# ProDoc_Board1_2026-06-09.net
KiCad netlist of a schematic drawn in EasyEDA Pro
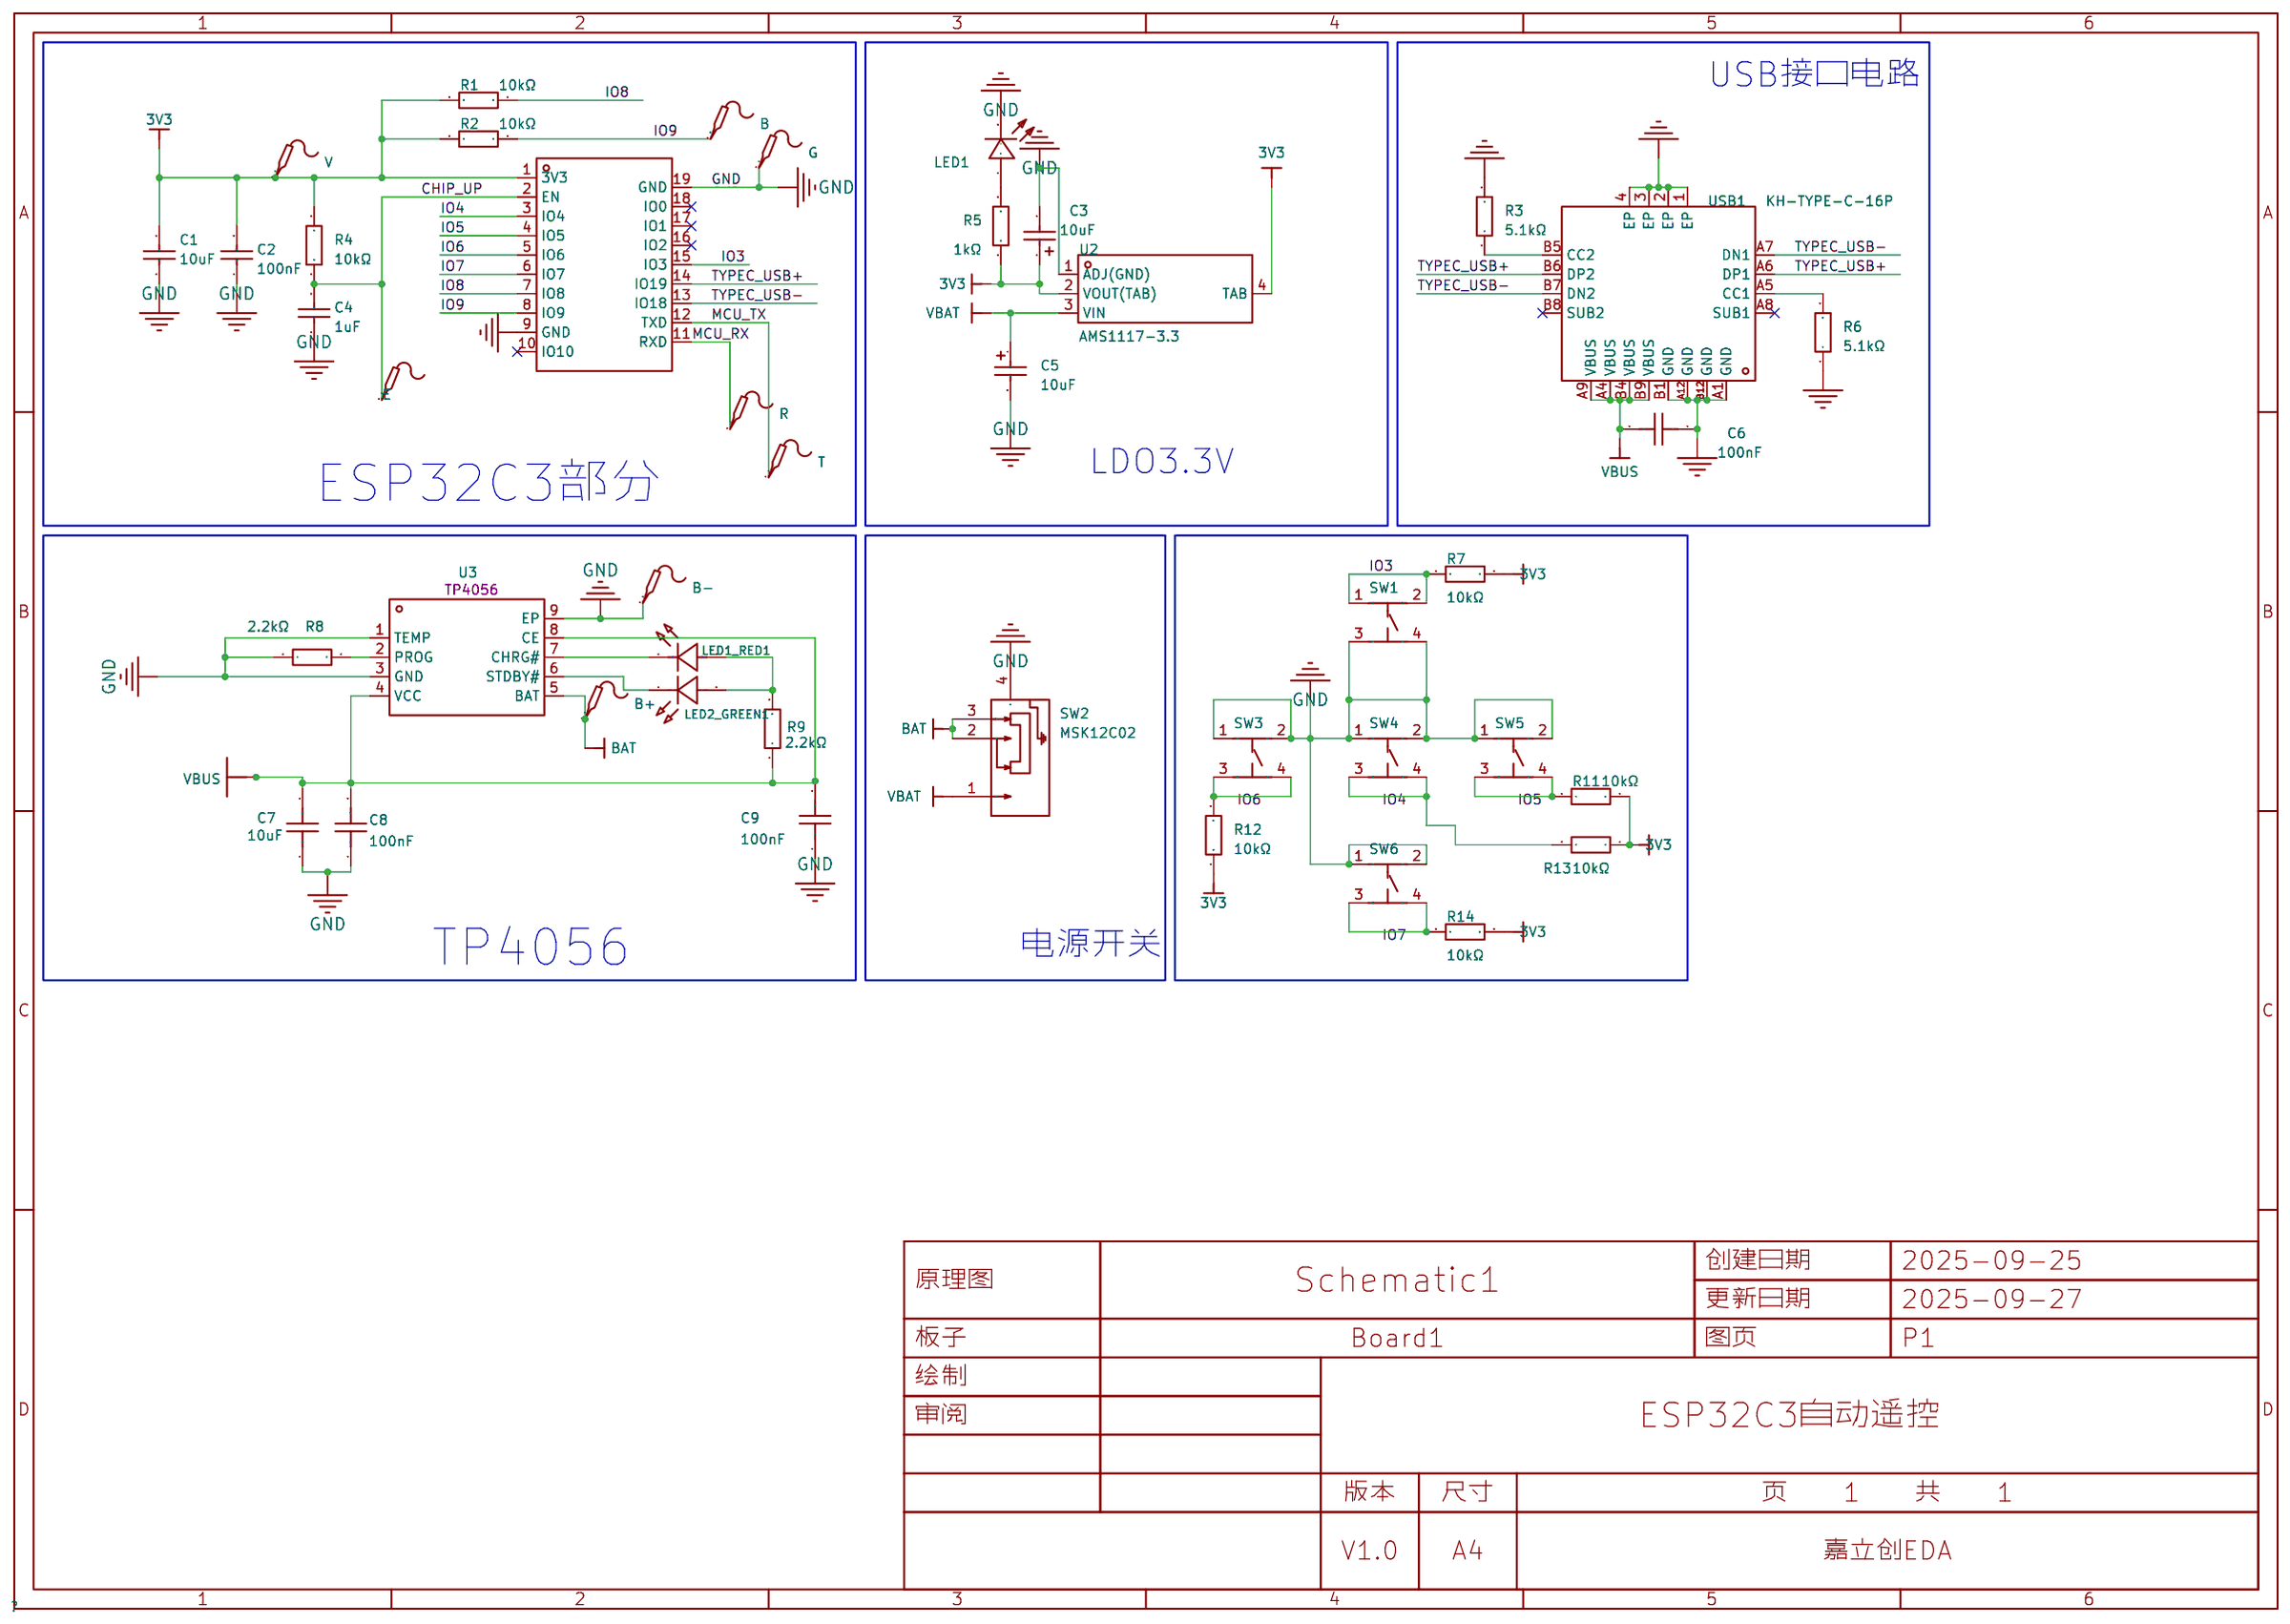
[diagram p0: schematic sheet]

(export (version "E")
  (design (tool "Eeschema 10.0.6"))
  (components
    (comp (ref "B")
      (value "~")
      (footprint "easyedapro:Test-Point-0.5mm")
      (libsource (lib "easyedapro") (part "Test-Point"))
    )
    (comp (ref "B+")
      (value "~")
      (footprint "easyedapro:Test-Point-0.5mm")
      (libsource (lib "easyedapro") (part "Test-Point"))
    )
    (comp (ref "B-")
      (value "~")
      (footprint "easyedapro:Test-Point-0.5mm")
      (libsource (lib "easyedapro") (part "Test-Point"))
    )
    (comp (ref "C1")
      (value "10uF")
      (footprint "easyedapro:C0805")
      (fields
        (field (name "Manufacturer Part") "CL21A106KOQNNNE")
        (field (name "Manufacturer") "SAMSUNG(三星)")
      )
      (libsource (lib "easyedapro") (part "CL21A106KOQNNNE"))
    )
    (comp (ref "C2")
      (value "100nF")
      (footprint "easyedapro:C0805")
      (fields (field (name "Manufacturer Part") "0805B104K500NT") (field (name "Manufacturer") "FH(风华)"))
      (libsource (lib "easyedapro") (part "0805B104K500NT"))
    )
    (comp (ref "C3")
      (value "10uF")
      (footprint "easyedapro:CAP-SMD_L3.2-W1.6-RD-C7171")
      (fields (field (name "Manufacturer Part") "TAJA106K016RNJ") (field (name "Manufacturer") "Kyocera AVX"))
      (libsource (lib "easyedapro") (part "TAJA106K016RNJ"))
    )
    (comp (ref "C4")
      (value "1uF")
      (footprint "easyedapro:C0805")
      (fields
        (field (name "Manufacturer Part") "CL21B105KBFNNNE")
        (field (name "Manufacturer") "SAMSUNG(三星)")
      )
      (libsource (lib "easyedapro") (part "CL21B105KBFNNNE"))
    )
    (comp (ref "C5")
      (value "10uF")
      (footprint "easyedapro:CAP-SMD_L3.2-W1.6-RD-C7171")
      (fields (field (name "Manufacturer Part") "TAJA106K016RNJ") (field (name "Manufacturer") "Kyocera AVX"))
      (libsource (lib "easyedapro") (part "TAJA106K016RNJ"))
    )
    (comp (ref "C6")
      (value "100nF")
      (footprint "easyedapro:C0603")
      (fields
        (field (name "Manufacturer Part") "CC0603KRX7R9BB104")
        (field (name "Manufacturer") "YAGEO(国巨)")
      )
      (libsource (lib "easyedapro") (part "CC0603KRX7R9BB104"))
    )
    (comp (ref "C7")
      (value "10uF")
      (footprint "easyedapro:C0603")
      (fields
        (field (name "Manufacturer Part") "CL10A106KP8NNNC")
        (field (name "Manufacturer") "SAMSUNG(三星)")
      )
      (libsource (lib "easyedapro") (part "CL10A106KP8NNNC"))
    )
    (comp (ref "C8")
      (value "100nF")
      (footprint "easyedapro:C0603")
      (fields
        (field (name "Manufacturer Part") "CC0603KRX7R9BB104")
        (field (name "Manufacturer") "YAGEO(国巨)")
      )
      (libsource (lib "easyedapro") (part "CC0603KRX7R9BB104"))
    )
    (comp (ref "C9")
      (value "100nF")
      (footprint "easyedapro:C0603")
      (fields
        (field (name "Manufacturer Part") "CC0603KRX7R9BB104")
        (field (name "Manufacturer") "YAGEO(国巨)")
      )
      (libsource (lib "easyedapro") (part "CC0603KRX7R9BB104"))
    )
    (comp (ref "E")
      (value "~")
      (footprint "easyedapro:Test-Point-0.5mm")
      (libsource (lib "easyedapro") (part "Test-Point"))
    )
    (comp (ref "G")
      (value "~")
      (footprint "easyedapro:Test-Point-0.5mm")
      (libsource (lib "easyedapro") (part "Test-Point"))
    )
    (comp (ref "LED1")
      (value "NCD0805R1")
      (footprint "easyedapro:LED0805-R-RD")
      (fields (field (name "Manufacturer") "国星光电"))
      (libsource (lib "easyedapro") (part "FC-2012HRK-620D"))
    )
    (comp (ref "LED1_RED1")
      (value "~")
      (footprint "easyedapro:LED0805-RD_RED")
      (fields
        (field (name "Manufacturer Part") "RF-OGB170TS-CB-E0")
        (field (name "Manufacturer") "Refond(瑞丰)")
      )
      (libsource (lib "easyedapro") (part "RF-OGB170TS-CB-E0"))
    )
    (comp (ref "LED2_GREEN1")
      (value "~")
      (footprint "easyedapro:LED0805-RD_GREEN")
      (fields (field (name "Manufacturer Part") "XL-2012UGC") (field (name "Manufacturer") "XINGLIGHT(成兴光)"))
      (libsource (lib "easyedapro") (part "XL-2012UGC"))
    )
    (comp (ref "R")
      (value "~")
      (footprint "easyedapro:Test-Point-0.5mm")
      (libsource (lib "easyedapro") (part "Test-Point"))
    )
    (comp (ref "R1")
      (value "10kΩ")
      (footprint "easyedapro:R0805")
      (fields
        (field (name "Manufacturer Part") "0805W8F1002T5E")
        (field (name "Manufacturer") "UNI-ROYAL(厚声)")
      )
      (libsource (lib "easyedapro") (part "0805W8F1002T5E"))
    )
    (comp (ref "R2")
      (value "10kΩ")
      (footprint "easyedapro:R0805")
      (fields
        (field (name "Manufacturer Part") "0805W8F1002T5E")
        (field (name "Manufacturer") "UNI-ROYAL(厚声)")
      )
      (libsource (lib "easyedapro") (part "0805W8F1002T5E"))
    )
    (comp (ref "R3")
      (value "5.1kΩ")
      (footprint "easyedapro:R0603")
      (fields
        (field (name "Manufacturer Part") "0603WAF5101T5E")
        (field (name "Manufacturer") "UNI-ROYAL(厚声)")
      )
      (libsource (lib "easyedapro") (part "0603WAF5101T5E"))
    )
    (comp (ref "R4")
      (value "10kΩ")
      (footprint "easyedapro:R0805")
      (fields
        (field (name "Manufacturer Part") "0805W8F1002T5E")
        (field (name "Manufacturer") "UNI-ROYAL(厚声)")
      )
      (libsource (lib "easyedapro") (part "0805W8F1002T5E"))
    )
    (comp (ref "R5")
      (value "1kΩ")
      (footprint "easyedapro:R0805")
      (fields (field (name "Manufacturer Part") "RC0805FR-071KL") (field (name "Manufacturer") "YAGEO(国巨)"))
      (libsource (lib "easyedapro") (part "RC0805FR-071KL"))
    )
    (comp (ref "R6")
      (value "5.1kΩ")
      (footprint "easyedapro:R0603")
      (fields
        (field (name "Manufacturer Part") "0603WAF5101T5E")
        (field (name "Manufacturer") "UNI-ROYAL(厚声)")
      )
      (libsource (lib "easyedapro") (part "0603WAF5101T5E"))
    )
    (comp (ref "R7")
      (value "10kΩ")
      (footprint "easyedapro:R0805")
      (fields
        (field (name "Manufacturer Part") "0805W8F1002T5E")
        (field (name "Manufacturer") "UNI-ROYAL(厚声)")
      )
      (libsource (lib "easyedapro") (part "0805W8F1002T5E"))
    )
    (comp (ref "R8")
      (value "2.2kΩ")
      (footprint "easyedapro:R0603")
      (fields
        (field (name "Manufacturer Part") "0603WAF2201T5E")
        (field (name "Manufacturer") "UNI-ROYAL(厚声)")
      )
      (libsource (lib "easyedapro") (part "0603WAF2201T5E"))
    )
    (comp (ref "R9")
      (value "2.2kΩ")
      (footprint "easyedapro:R0603")
      (fields
        (field (name "Manufacturer Part") "0603WAF2201T5E")
        (field (name "Manufacturer") "UNI-ROYAL(厚声)")
      )
      (libsource (lib "easyedapro") (part "0603WAF2201T5E"))
    )
    (comp (ref "R11")
      (value "10kΩ")
      (footprint "easyedapro:R0805")
      (fields
        (field (name "Manufacturer Part") "0805W8F1002T5E")
        (field (name "Manufacturer") "UNI-ROYAL(厚声)")
      )
      (libsource (lib "easyedapro") (part "0805W8F1002T5E"))
    )
    (comp (ref "R12")
      (value "10kΩ")
      (footprint "easyedapro:R0805")
      (fields
        (field (name "Manufacturer Part") "0805W8F1002T5E")
        (field (name "Manufacturer") "UNI-ROYAL(厚声)")
      )
      (libsource (lib "easyedapro") (part "0805W8F1002T5E"))
    )
    (comp (ref "R13")
      (value "10kΩ")
      (footprint "easyedapro:R0805")
      (fields
        (field (name "Manufacturer Part") "0805W8F1002T5E")
        (field (name "Manufacturer") "UNI-ROYAL(厚声)")
      )
      (libsource (lib "easyedapro") (part "0805W8F1002T5E"))
    )
    (comp (ref "R14")
      (value "10kΩ")
      (footprint "easyedapro:R0805")
      (fields
        (field (name "Manufacturer Part") "0805W8F1002T5E")
        (field (name "Manufacturer") "UNI-ROYAL(厚声)")
      )
      (libsource (lib "easyedapro") (part "0805W8F1002T5E"))
    )
    (comp (ref "SW1")
      (value "KH-6X6X5H-STM")
      (footprint "easyedapro:SW-SMD_4P-L6.0-W6.0-P4.50-LS9.0_H5.0")
      (fields (field (name "Manufacturer") "kinghelm(金航标)"))
      (libsource (lib "easyedapro") (part "KH-6X6X5H-STM"))
    )
    (comp (ref "SW2")
      (value "MSK12C02")
      (footprint "easyedapro:SW-TH_MSK12C02")
      (fields (field (name "Manufacturer") "SHOU HAN(首韩)"))
      (libsource (lib "easyedapro") (part "MSK12C02"))
    )
    (comp (ref "SW3")
      (value "KH-6X6X5H-STM")
      (footprint "easyedapro:SW-SMD_4P-L6.0-W6.0-P4.50-LS9.0_H5.0")
      (fields (field (name "Manufacturer") "kinghelm(金航标)"))
      (libsource (lib "easyedapro") (part "KH-6X6X5H-STM"))
    )
    (comp (ref "SW4")
      (value "KH-6X6X5H-STM")
      (footprint "easyedapro:SW-SMD_4P-L6.0-W6.0-P4.50-LS9.0_H5.0")
      (fields (field (name "Manufacturer") "kinghelm(金航标)"))
      (libsource (lib "easyedapro") (part "KH-6X6X5H-STM"))
    )
    (comp (ref "SW5")
      (value "KH-6X6X5H-STM")
      (footprint "easyedapro:SW-SMD_4P-L6.0-W6.0-P4.50-LS9.0_H5.0")
      (fields (field (name "Manufacturer") "kinghelm(金航标)"))
      (libsource (lib "easyedapro") (part "KH-6X6X5H-STM"))
    )
    (comp (ref "SW6")
      (value "KH-6X6X5H-STM")
      (footprint "easyedapro:SW-SMD_4P-L6.0-W6.0-P4.50-LS9.0_H5.0")
      (fields (field (name "Manufacturer") "kinghelm(金航标)"))
      (libsource (lib "easyedapro") (part "KH-6X6X5H-STM"))
    )
    (comp (ref "T")
      (value "~")
      (footprint "easyedapro:Test-Point-0.5mm")
      (libsource (lib "easyedapro") (part "Test-Point"))
    )
    (comp (ref "U1")
      (value "ESP32-C3-WROOM-02-H4")
      (footprint "easyedapro:WIFIM-SMD_18P-L20.0-W18.0-P1.50")
      (fields (field (name "Manufacturer") "ESPRESSIF(乐鑫)"))
      (libsource (lib "easyedapro") (part "ESP32-C3-WROOM-02-H4"))
    )
    (comp (ref "U2")
      (value "AMS1117-3.3")
      (footprint "easyedapro:SOT-223-4_L6.5-W3.5-P2.30-LS7.0-BR")
      (description "输出类型:固定;最大输入电压:18V;输出电压:3.3V;输出电流:1A;电源纹波抑制比(PSRR):60dB@(120Hz);输出极性:正极;")
      (fields (field (name "Manufacturer") "UMW(友台半导体)"))
      (libsource (lib "easyedapro") (part "AMS1117-3.3_C347222"))
    )
    (comp (ref "U3")
      (value "~")
      (footprint "easyedapro:ESOP-8_L4.9-W3.9-P1.27-LS6.0-BL-EP")
      (description "充电电池的类型:-;电池单元组数:-;最大充电电流:-;充满的电池组电压:-;最大供应电压:-;")
      (fields (field (name "Manufacturer Part") "TP4056") (field (name "Manufacturer") "TPOWER(天源)"))
      (libsource (lib "easyedapro") (part "TP4056_C382139"))
    )
    (comp (ref "USB1")
      (value "KH-TYPE-C-16P")
      (footprint "easyedapro:USB-C-SMD_KH-TYPE-C-16P")
      (fields (field (name "Manufacturer") "kinghelm(金航标)"))
      (libsource (lib "easyedapro") (part "KH-TYPE-C-16P"))
    )
    (comp (ref "V")
      (value "~")
      (footprint "easyedapro:Test-Point-0.5mm")
      (libsource (lib "easyedapro") (part "Test-Point"))
    )
  )
  (nets
    (net (code "1") (name "/CHIP_UP") (class "Default")
      (node (ref "C4") (pin "2") (pinfunction "2_2") (pintype "input"))
      (node (ref "E") (pin "1") (pinfunction "1_1") (pintype "input"))
      (node (ref "R4") (pin "1") (pinfunction "1_1") (pintype "input"))
      (node (ref "U1") (pin "2") (pinfunction "EN_2") (pintype "unspecified"))
    )
    (net (code "2") (name "/IO3") (class "Default")
      (node (ref "R7") (pin "2") (pinfunction "2_2") (pintype "input"))
      (node (ref "SW1") (pin "1") (pinfunction "1_1") (pintype "unspecified"))
      (node (ref "SW1") (pin "2") (pinfunction "2_2") (pintype "unspecified"))
      (node (ref "U1") (pin "15") (pinfunction "IO3_15") (pintype "unspecified"))
    )
    (net (code "3") (name "/IO4") (class "Default")
      (node (ref "R13") (pin "2") (pinfunction "2_2") (pintype "input"))
      (node (ref "SW4") (pin "3") (pinfunction "3_3") (pintype "unspecified"))
      (node (ref "SW4") (pin "4") (pinfunction "4_4") (pintype "unspecified"))
      (node (ref "U1") (pin "3") (pinfunction "IO4_3") (pintype "unspecified"))
    )
    (net (code "4") (name "/IO5") (class "Default")
      (node (ref "R11") (pin "2") (pinfunction "2_2") (pintype "input"))
      (node (ref "SW5") (pin "3") (pinfunction "3_3") (pintype "unspecified"))
      (node (ref "SW5") (pin "4") (pinfunction "4_4") (pintype "unspecified"))
      (node (ref "U1") (pin "4") (pinfunction "IO5_4") (pintype "unspecified"))
    )
    (net (code "5") (name "/IO6") (class "Default")
      (node (ref "R12") (pin "2") (pinfunction "2_2") (pintype "input"))
      (node (ref "SW3") (pin "3") (pinfunction "3_3") (pintype "unspecified"))
      (node (ref "SW3") (pin "4") (pinfunction "4_4") (pintype "unspecified"))
      (node (ref "U1") (pin "5") (pinfunction "IO6_5") (pintype "unspecified"))
    )
    (net (code "6") (name "/IO7") (class "Default")
      (node (ref "R14") (pin "2") (pinfunction "2_2") (pintype "input"))
      (node (ref "SW6") (pin "3") (pinfunction "3_3") (pintype "unspecified"))
      (node (ref "SW6") (pin "4") (pinfunction "4_4") (pintype "unspecified"))
      (node (ref "U1") (pin "6") (pinfunction "IO7_6") (pintype "unspecified"))
    )
    (net (code "7") (name "/IO8") (class "Default")
      (node (ref "R1") (pin "1") (pinfunction "1_1") (pintype "input"))
      (node (ref "U1") (pin "7") (pinfunction "IO8_7") (pintype "unspecified"))
    )
    (net (code "8") (name "/IO9") (class "Default")
      (node (ref "B") (pin "1") (pinfunction "1_1") (pintype "input"))
      (node (ref "R2") (pin "1") (pinfunction "1_1") (pintype "input"))
      (node (ref "U1") (pin "8") (pinfunction "IO9_8") (pintype "unspecified"))
    )
    (net (code "9") (name "/MCU_RX") (class "Default")
      (node (ref "R") (pin "1") (pinfunction "1_1") (pintype "input"))
      (node (ref "U1") (pin "11") (pinfunction "RXD_11") (pintype "unspecified"))
    )
    (net (code "10") (name "/MCU_TX") (class "Default")
      (node (ref "T") (pin "1") (pinfunction "1_1") (pintype "input"))
      (node (ref "U1") (pin "12") (pinfunction "TXD_12") (pintype "unspecified"))
    )
    (net (code "11") (name "/TYPEC_USB+") (class "Default")
      (node (ref "U1") (pin "14") (pinfunction "IO19_14") (pintype "unspecified"))
      (node (ref "USB1") (pin "A6") (pinfunction "DP1_A6") (pintype "input"))
      (node (ref "USB1") (pin "B6") (pinfunction "DP2_B6") (pintype "input"))
    )
    (net (code "12") (name "/TYPEC_USB-") (class "Default")
      (node (ref "U1") (pin "13") (pinfunction "IO18_13") (pintype "unspecified"))
      (node (ref "USB1") (pin "A7") (pinfunction "DN1_A7") (pintype "input"))
      (node (ref "USB1") (pin "B7") (pinfunction "DN2_B7") (pintype "input"))
    )
    (net (code "13") (name "3V3") (class "Default")
      (node (ref "C1") (pin "2") (pinfunction "2_2") (pintype "input"))
      (node (ref "C2") (pin "2") (pinfunction "2_2") (pintype "input"))
      (node (ref "C3") (pin "1") (pinfunction "1_1") (pintype "input"))
      (node (ref "R1") (pin "2") (pinfunction "2_2") (pintype "input"))
      (node (ref "R11") (pin "1") (pinfunction "1_1") (pintype "input"))
      (node (ref "R12") (pin "1") (pinfunction "1_1") (pintype "input"))
      (node (ref "R13") (pin "1") (pinfunction "1_1") (pintype "input"))
      (node (ref "R14") (pin "1") (pinfunction "1_1") (pintype "input"))
      (node (ref "R2") (pin "2") (pinfunction "2_2") (pintype "input"))
      (node (ref "R4") (pin "2") (pinfunction "2_2") (pintype "input"))
      (node (ref "R5") (pin "1") (pinfunction "1_1") (pintype "input"))
      (node (ref "R7") (pin "1") (pinfunction "1_1") (pintype "input"))
      (node (ref "U1") (pin "1") (pinfunction "3V3_1") (pintype "unspecified"))
      (node (ref "U2") (pin "2") (pinfunction "VOUT(TAB)_2") (pintype "input"))
      (node (ref "U2") (pin "4") (pinfunction "TAB_4") (pintype "input"))
      (node (ref "V") (pin "1") (pinfunction "1_1") (pintype "input"))
    )
    (net (code "14") (name "BAT") (class "Default")
      (node (ref "B+") (pin "1") (pinfunction "1_1") (pintype "input"))
      (node (ref "SW2") (pin "2") (pinfunction "2_2") (pintype "unspecified"))
      (node (ref "SW2") (pin "3") (pinfunction "3_3") (pintype "unspecified"))
      (node (ref "U3") (pin "5") (pinfunction "BAT_5") (pintype "input"))
    )
    (net (code "15") (name "GND") (class "Default")
      (node (ref "B-") (pin "1") (pinfunction "1_1") (pintype "input"))
      (node (ref "C1") (pin "1") (pinfunction "1_1") (pintype "input"))
      (node (ref "C2") (pin "1") (pinfunction "1_1") (pintype "input"))
      (node (ref "C3") (pin "2") (pinfunction "2_2") (pintype "input"))
      (node (ref "C4") (pin "1") (pinfunction "1_1") (pintype "input"))
      (node (ref "C5") (pin "2") (pinfunction "2_2") (pintype "input"))
      (node (ref "C6") (pin "1") (pinfunction "1_1") (pintype "unspecified"))
      (node (ref "C7") (pin "1") (pinfunction "1_1") (pintype "unspecified"))
      (node (ref "C8") (pin "1") (pinfunction "1_1") (pintype "unspecified"))
      (node (ref "C9") (pin "1") (pinfunction "1_1") (pintype "unspecified"))
      (node (ref "G") (pin "1") (pinfunction "1_1") (pintype "input"))
      (node (ref "LED1") (pin "2") (pinfunction "-_2") (pintype "unspecified"))
      (node (ref "R3") (pin "2") (pinfunction "2_2") (pintype "input"))
      (node (ref "R6") (pin "1") (pinfunction "1_1") (pintype "input"))
      (node (ref "R8") (pin "1") (pinfunction "1_1") (pintype "input"))
      (node (ref "SW1") (pin "3") (pinfunction "3_3") (pintype "unspecified"))
      (node (ref "SW1") (pin "4") (pinfunction "4_4") (pintype "unspecified"))
      (node (ref "SW2") (pin "4") (pinfunction "4_4") (pintype "unspecified"))
      (node (ref "SW3") (pin "1") (pinfunction "1_1") (pintype "unspecified"))
      (node (ref "SW3") (pin "2") (pinfunction "2_2") (pintype "unspecified"))
      (node (ref "SW4") (pin "1") (pinfunction "1_1") (pintype "unspecified"))
      (node (ref "SW4") (pin "2") (pinfunction "2_2") (pintype "unspecified"))
      (node (ref "SW5") (pin "1") (pinfunction "1_1") (pintype "unspecified"))
      (node (ref "SW5") (pin "2") (pinfunction "2_2") (pintype "unspecified"))
      (node (ref "SW6") (pin "1") (pinfunction "1_1") (pintype "unspecified"))
      (node (ref "SW6") (pin "2") (pinfunction "2_2") (pintype "unspecified"))
      (node (ref "U1") (pin "19") (pinfunction "GND_19") (pintype "unspecified"))
      (node (ref "U1") (pin "9") (pinfunction "GND_9") (pintype "unspecified"))
      (node (ref "U2") (pin "1") (pinfunction "ADJ(GND)_1") (pintype "input"))
      (node (ref "U3") (pin "1") (pinfunction "TEMP_1") (pintype "input"))
      (node (ref "U3") (pin "3") (pinfunction "GND_3") (pintype "input"))
      (node (ref "U3") (pin "9") (pinfunction "EP_9") (pintype "input"))
      (node (ref "USB1") (pin "1") (pinfunction "EP_1") (pintype "input"))
      (node (ref "USB1") (pin "2") (pinfunction "EP_2") (pintype "input"))
      (node (ref "USB1") (pin "3") (pinfunction "EP_3") (pintype "input"))
      (node (ref "USB1") (pin "4") (pinfunction "EP_4") (pintype "input"))
      (node (ref "USB1") (pin "A1") (pinfunction "GND_A1") (pintype "input"))
      (node (ref "USB1") (pin "A12") (pinfunction "GND_A12") (pintype "input"))
      (node (ref "USB1") (pin "B1") (pinfunction "GND_B1") (pintype "input"))
      (node (ref "USB1") (pin "B12") (pinfunction "GND_B12") (pintype "input"))
    )
    (net (code "16") (name "Net-(LED1-+)") (class "Default")
      (node (ref "LED1") (pin "1") (pinfunction "+_1") (pintype "unspecified"))
      (node (ref "R5") (pin "2") (pinfunction "2_2") (pintype "input"))
    )
    (net (code "17") (name "Net-(LED1_RED1-A)") (class "Default")
      (node (ref "LED1_RED1") (pin "2") (pinfunction "A_2") (pintype "input"))
      (node (ref "LED2_GREEN1") (pin "2") (pinfunction "A_2") (pintype "input"))
      (node (ref "R9") (pin "2") (pinfunction "2_2") (pintype "input"))
    )
    (net (code "18") (name "Net-(LED1_RED1-K)") (class "Default")
      (node (ref "LED1_RED1") (pin "1") (pinfunction "K_1") (pintype "input"))
      (node (ref "U3") (pin "7") (pinfunction "CHRG#_7") (pintype "input"))
    )
    (net (code "19") (name "Net-(LED2_GREEN1-K)") (class "Default")
      (node (ref "LED2_GREEN1") (pin "1") (pinfunction "K_1") (pintype "input"))
      (node (ref "U3") (pin "6") (pinfunction "STDBY#_6") (pintype "input"))
    )
    (net (code "20") (name "Net-(U3-PROG)") (class "Default")
      (node (ref "R8") (pin "2") (pinfunction "2_2") (pintype "input"))
      (node (ref "U3") (pin "2") (pinfunction "PROG_2") (pintype "input"))
    )
    (net (code "21") (name "Net-(USB1-CC1)") (class "Default")
      (node (ref "R6") (pin "2") (pinfunction "2_2") (pintype "input"))
      (node (ref "USB1") (pin "A5") (pinfunction "CC1_A5") (pintype "input"))
    )
    (net (code "22") (name "Net-(USB1-CC2)") (class "Default")
      (node (ref "R3") (pin "1") (pinfunction "1_1") (pintype "input"))
      (node (ref "USB1") (pin "B5") (pinfunction "CC2_B5") (pintype "input"))
    )
    (net (code "23") (name "VBAT") (class "Default")
      (node (ref "C5") (pin "1") (pinfunction "1_1") (pintype "input"))
      (node (ref "SW2") (pin "1") (pinfunction "1_1") (pintype "unspecified"))
      (node (ref "U2") (pin "3") (pinfunction "VIN_3") (pintype "input"))
    )
    (net (code "24") (name "VBUS") (class "Default")
      (node (ref "C6") (pin "2") (pinfunction "2_2") (pintype "unspecified"))
      (node (ref "C7") (pin "2") (pinfunction "2_2") (pintype "unspecified"))
      (node (ref "C8") (pin "2") (pinfunction "2_2") (pintype "unspecified"))
      (node (ref "C9") (pin "2") (pinfunction "2_2") (pintype "unspecified"))
      (node (ref "R9") (pin "1") (pinfunction "1_1") (pintype "input"))
      (node (ref "U3") (pin "4") (pinfunction "VCC_4") (pintype "input"))
      (node (ref "U3") (pin "8") (pinfunction "CE_8") (pintype "input"))
      (node (ref "USB1") (pin "A4") (pinfunction "VBUS_A4") (pintype "input"))
      (node (ref "USB1") (pin "A9") (pinfunction "VBUS_A9") (pintype "input"))
      (node (ref "USB1") (pin "B4") (pinfunction "VBUS_B4") (pintype "input"))
      (node (ref "USB1") (pin "B9") (pinfunction "VBUS_B9") (pintype "input"))
    )
    (net (code "25") (name "unconnected-(U1-IO0-Pad18)") (class "Default")
      (node (ref "U1") (pin "18") (pinfunction "IO0_18") (pintype "unspecified+no_connect"))
    )
    (net (code "26") (name "unconnected-(U1-IO1-Pad17)") (class "Default")
      (node (ref "U1") (pin "17") (pinfunction "IO1_17") (pintype "unspecified+no_connect"))
    )
    (net (code "27") (name "unconnected-(U1-IO2-Pad16)") (class "Default")
      (node (ref "U1") (pin "16") (pinfunction "IO2_16") (pintype "unspecified+no_connect"))
    )
    (net (code "28") (name "unconnected-(U1-IO10-Pad10)") (class "Default")
      (node (ref "U1") (pin "10") (pinfunction "IO10_10") (pintype "unspecified+no_connect"))
    )
    (net (code "29") (name "unconnected-(USB1-SUB1-PadA8)") (class "Default")
      (node (ref "USB1") (pin "A8") (pinfunction "SUB1_A8") (pintype "input+no_connect"))
    )
    (net (code "30") (name "unconnected-(USB1-SUB2-PadB8)") (class "Default")
      (node (ref "USB1") (pin "B8") (pinfunction "SUB2_B8") (pintype "input+no_connect"))
    )
  )
)
